# PLWD_Battery_Charger.net
KiCad netlist of a schematic drawn in Altium Designer
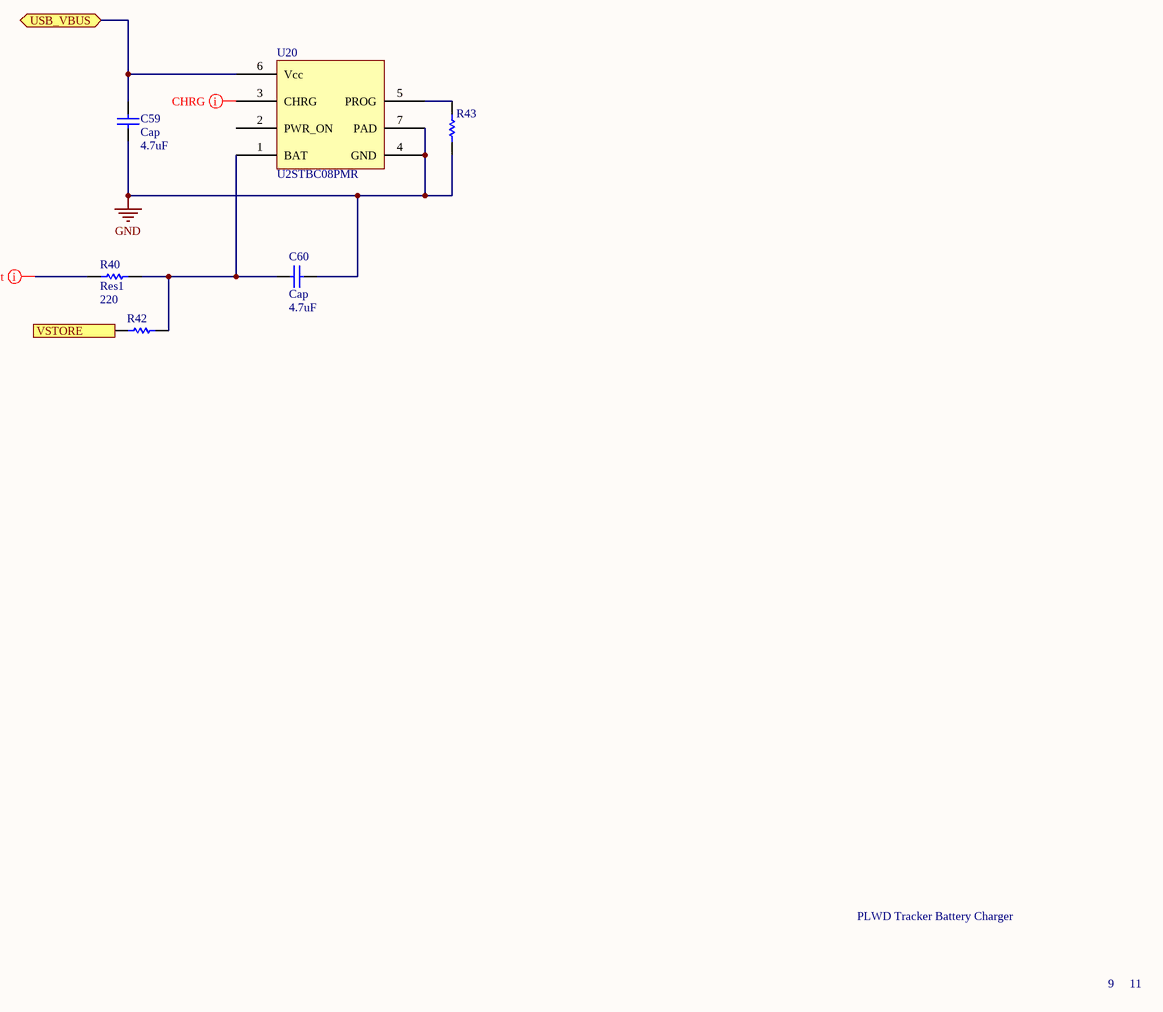
[diagram p0: PLWD_Battery_Charger.SchDoc]

(export (version "E")
  (design (tool "Eeschema 10.0.6"))
  (components
    (comp (ref "C59")
      (value "Cap")
      (footprint "RAD-0.3")
      (description "Capacitor")
      (fields (field (name "ALTIUM_VALUE") "4.7uF") (field (name "PUBLISHER") "Altium Limited"))
      (libsource (lib "Miscellaneous Devices") (part "Cap"))
    )
    (comp (ref "C60")
      (value "Cap")
      (footprint "RAD-0.3")
      (description "Capacitor")
      (fields (field (name "ALTIUM_VALUE") "4.7uF") (field (name "PUBLISHER") "Altium Limited"))
      (libsource (lib "Miscellaneous Devices") (part "Cap"))
    )
    (comp (ref "R40")
      (value "Res1")
      (footprint "AXIAL-0.3")
      (description "Resistor")
      (fields (field (name "ALTIUM_VALUE") "220") (field (name "PUBLISHER") "Altium Limited"))
      (libsource (lib "Miscellaneous Devices") (part "Res1"))
    )
    (comp (ref "R42")
      (value "Res1")
      (footprint "AXIAL-0.3")
      (description "Resistor")
      (fields (field (name "PUBLISHER") "Altium Limited"))
      (libsource (lib "Miscellaneous Devices") (part "Res1"))
    )
    (comp (ref "R43")
      (value "Res1")
      (footprint "AXIAL-0.3")
      (description "Resistor")
      (fields (field (name "PUBLISHER") "Altium Limited"))
      (libsource (lib "Miscellaneous Devices") (part "Res1"))
    )
    (comp (ref "U20") (value "U2STBC08PMR") (libsource (lib "PLWD_PartLib") (part "U2STBC08PMR")))
  )
  (nets
    (net (code "1") (name "/USB_VBUS") (class "Default")
      (node (ref "C59") (pin "2") (pinfunction "2_2") (pintype "passive"))
      (node (ref "U20") (pin "6") (pinfunction "Vcc_6") (pintype "passive"))
    )
    (net (code "2") (name "/VSTORE") (class "Default")
      (node (ref "R42") (pin "1") (pinfunction "1_1") (pintype "passive"))
    )
    (net (code "3") (name "GND") (class "Default")
      (node (ref "C59") (pin "1") (pinfunction "1_1") (pintype "passive"))
      (node (ref "C60") (pin "1") (pinfunction "1_1") (pintype "passive"))
      (node (ref "R43") (pin "2") (pinfunction "2_2") (pintype "passive"))
      (node (ref "U20") (pin "4") (pinfunction "GND_4") (pintype "passive"))
      (node (ref "U20") (pin "7") (pinfunction "PAD_7") (pintype "passive"))
    )
    (net (code "4") (name "Net-(U20-BAT)") (class "Default")
      (node (ref "C60") (pin "2") (pinfunction "2_2") (pintype "passive"))
      (node (ref "R40") (pin "2") (pinfunction "2_2") (pintype "passive"))
      (node (ref "R42") (pin "2") (pinfunction "2_2") (pintype "passive"))
      (node (ref "U20") (pin "1") (pinfunction "BAT_1") (pintype "passive"))
    )
    (net (code "5") (name "Net-(U20-PROG)") (class "Default")
      (node (ref "R43") (pin "1") (pinfunction "1_1") (pintype "passive"))
      (node (ref "U20") (pin "5") (pinfunction "PROG_5") (pintype "passive"))
    )
    (net (code "6") (name "unconnected-(R40-Pad1)") (class "Default")
      (node (ref "R40") (pin "1") (pinfunction "1_1") (pintype "passive"))
    )
    (net (code "7") (name "unconnected-(U20-CHRG-Pad3)") (class "Default")
      (node (ref "U20") (pin "3") (pinfunction "CHRG_3") (pintype "passive"))
    )
    (net (code "8") (name "unconnected-(U20-PWR_ON-Pad2)") (class "Default")
      (node (ref "U20") (pin "2") (pinfunction "PWR_ON_2") (pintype "passive"))
    )
  )
)
